# Power.net
KiCad netlist of a schematic drawn in Altium Designer
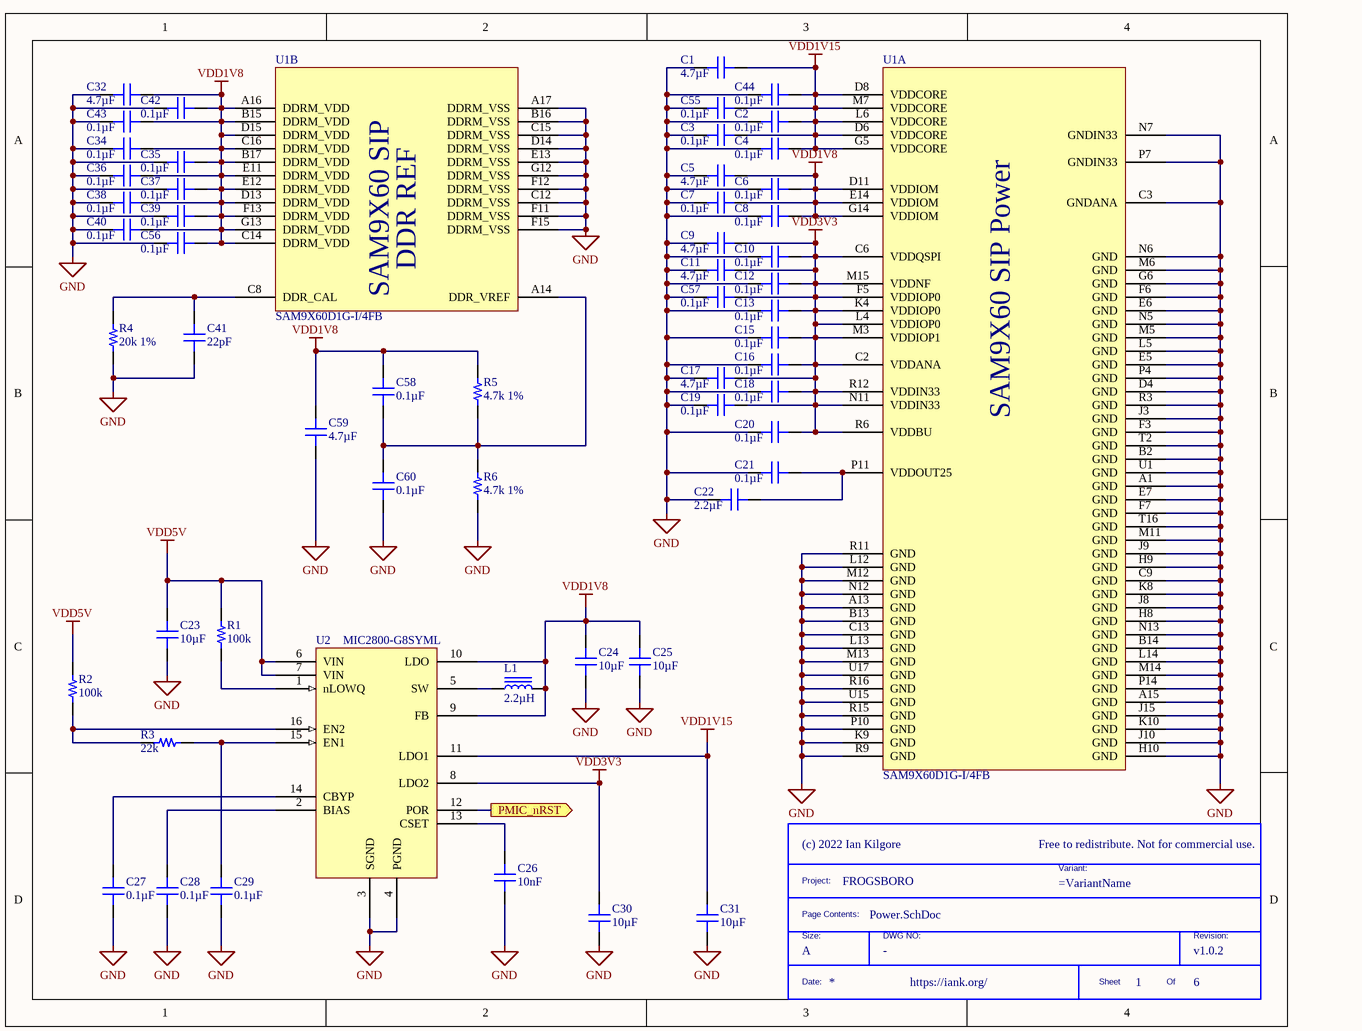
[diagram p0: Power.SchDoc]

(export (version "E")
  (design (tool "Eeschema 10.0.6"))
  (components
    (comp (ref "C1")
      (value "4.7µF")
      (footprint "CAP 0402_1005")
      (description "CAP CER 4.7UF 10V X5R 0402")
      (fields
        (field (name "PART NUMBER") "CL05A475KP5NRNC")
        (field (name "MANUFACTURER") "Samsung Electro-Mechanics")
      )
      (libsource (lib "Celestial Altium Library - altium_library") (part "Capacitor"))
    )
    (comp (ref "C2")
      (value "0.1µF")
      (footprint "CAP 0402_1005")
      (description "CAP CER 0.1UF 16V X5R 0402")
      (fields (field (name "PART NUMBER") "C0402C104K4PACTU") (field (name "MANUFACTURER") "KEMET"))
      (libsource (lib "Celestial Altium Library - altium_library") (part "Capacitor"))
    )
    (comp (ref "C3")
      (value "0.1µF")
      (footprint "CAP 0402_1005")
      (description "CAP CER 0.1UF 16V X5R 0402")
      (fields (field (name "PART NUMBER") "C0402C104K4PACTU") (field (name "MANUFACTURER") "KEMET"))
      (libsource (lib "Celestial Altium Library - altium_library") (part "Capacitor"))
    )
    (comp (ref "C4")
      (value "0.1µF")
      (footprint "CAP 0402_1005")
      (description "CAP CER 0.1UF 16V X5R 0402")
      (fields (field (name "PART NUMBER") "C0402C104K4PACTU") (field (name "MANUFACTURER") "KEMET"))
      (libsource (lib "Celestial Altium Library - altium_library") (part "Capacitor"))
    )
    (comp (ref "C5")
      (value "4.7µF")
      (footprint "CAP 0402_1005")
      (description "CAP CER 4.7UF 10V X5R 0402")
      (fields
        (field (name "PART NUMBER") "CL05A475KP5NRNC")
        (field (name "MANUFACTURER") "Samsung Electro-Mechanics")
      )
      (libsource (lib "Celestial Altium Library - altium_library") (part "Capacitor"))
    )
    (comp (ref "C6")
      (value "0.1µF")
      (footprint "CAP 0402_1005")
      (description "CAP CER 0.1UF 16V X5R 0402")
      (fields (field (name "PART NUMBER") "C0402C104K4PACTU") (field (name "MANUFACTURER") "KEMET"))
      (libsource (lib "Celestial Altium Library - altium_library") (part "Capacitor"))
    )
    (comp (ref "C7")
      (value "0.1µF")
      (footprint "CAP 0402_1005")
      (description "CAP CER 0.1UF 16V X5R 0402")
      (fields (field (name "PART NUMBER") "C0402C104K4PACTU") (field (name "MANUFACTURER") "KEMET"))
      (libsource (lib "Celestial Altium Library - altium_library") (part "Capacitor"))
    )
    (comp (ref "C8")
      (value "0.1µF")
      (footprint "CAP 0402_1005")
      (description "CAP CER 0.1UF 16V X5R 0402")
      (fields (field (name "PART NUMBER") "C0402C104K4PACTU") (field (name "MANUFACTURER") "KEMET"))
      (libsource (lib "Celestial Altium Library - altium_library") (part "Capacitor"))
    )
    (comp (ref "C9")
      (value "4.7µF")
      (footprint "CAP 0402_1005")
      (description "CAP CER 4.7UF 10V X5R 0402")
      (fields
        (field (name "PART NUMBER") "CL05A475KP5NRNC")
        (field (name "MANUFACTURER") "Samsung Electro-Mechanics")
      )
      (libsource (lib "Celestial Altium Library - altium_library") (part "Capacitor"))
    )
    (comp (ref "C10")
      (value "0.1µF")
      (footprint "CAP 0402_1005")
      (description "CAP CER 0.1UF 16V X5R 0402")
      (fields (field (name "PART NUMBER") "C0402C104K4PACTU") (field (name "MANUFACTURER") "KEMET"))
      (libsource (lib "Celestial Altium Library - altium_library") (part "Capacitor"))
    )
    (comp (ref "C11")
      (value "4.7µF")
      (footprint "CAP 0402_1005")
      (description "CAP CER 4.7UF 10V X5R 0402")
      (fields
        (field (name "PART NUMBER") "CL05A475KP5NRNC")
        (field (name "MANUFACTURER") "Samsung Electro-Mechanics")
      )
      (libsource (lib "Celestial Altium Library - altium_library") (part "Capacitor"))
    )
    (comp (ref "C12")
      (value "0.1µF")
      (footprint "CAP 0402_1005")
      (description "CAP CER 0.1UF 16V X5R 0402")
      (fields (field (name "PART NUMBER") "C0402C104K4PACTU") (field (name "MANUFACTURER") "KEMET"))
      (libsource (lib "Celestial Altium Library - altium_library") (part "Capacitor"))
    )
    (comp (ref "C13")
      (value "0.1µF")
      (footprint "CAP 0402_1005")
      (description "CAP CER 0.1UF 16V X5R 0402")
      (fields (field (name "PART NUMBER") "C0402C104K4PACTU") (field (name "MANUFACTURER") "KEMET"))
      (libsource (lib "Celestial Altium Library - altium_library") (part "Capacitor"))
    )
    (comp (ref "C15")
      (value "0.1µF")
      (footprint "CAP 0402_1005")
      (description "CAP CER 0.1UF 16V X5R 0402")
      (fields (field (name "PART NUMBER") "C0402C104K4PACTU") (field (name "MANUFACTURER") "KEMET"))
      (libsource (lib "Celestial Altium Library - altium_library") (part "Capacitor"))
    )
    (comp (ref "C16")
      (value "0.1µF")
      (footprint "CAP 0402_1005")
      (description "CAP CER 0.1UF 16V X5R 0402")
      (fields (field (name "PART NUMBER") "C0402C104K4PACTU") (field (name "MANUFACTURER") "KEMET"))
      (libsource (lib "Celestial Altium Library - altium_library") (part "Capacitor"))
    )
    (comp (ref "C17")
      (value "4.7µF")
      (footprint "CAP 0402_1005")
      (description "CAP CER 4.7UF 10V X5R 0402")
      (fields
        (field (name "PART NUMBER") "CL05A475KP5NRNC")
        (field (name "MANUFACTURER") "Samsung Electro-Mechanics")
      )
      (libsource (lib "Celestial Altium Library - altium_library") (part "Capacitor"))
    )
    (comp (ref "C18")
      (value "0.1µF")
      (footprint "CAP 0402_1005")
      (description "CAP CER 0.1UF 16V X5R 0402")
      (fields (field (name "PART NUMBER") "C0402C104K4PACTU") (field (name "MANUFACTURER") "KEMET"))
      (libsource (lib "Celestial Altium Library - altium_library") (part "Capacitor"))
    )
    (comp (ref "C19")
      (value "0.1µF")
      (footprint "CAP 0402_1005")
      (description "CAP CER 0.1UF 16V X5R 0402")
      (fields (field (name "PART NUMBER") "C0402C104K4PACTU") (field (name "MANUFACTURER") "KEMET"))
      (libsource (lib "Celestial Altium Library - altium_library") (part "Capacitor"))
    )
    (comp (ref "C20")
      (value "0.1µF")
      (footprint "CAP 0402_1005")
      (description "CAP CER 0.1UF 16V X5R 0402")
      (fields (field (name "PART NUMBER") "C0402C104K4PACTU") (field (name "MANUFACTURER") "KEMET"))
      (libsource (lib "Celestial Altium Library - altium_library") (part "Capacitor"))
    )
    (comp (ref "C21")
      (value "0.1µF")
      (footprint "CAP 0402_1005")
      (description "CAP CER 0.1UF 16V X5R 0402")
      (fields (field (name "PART NUMBER") "C0402C104K4PACTU") (field (name "MANUFACTURER") "KEMET"))
      (libsource (lib "Celestial Altium Library - altium_library") (part "Capacitor"))
    )
    (comp (ref "C22")
      (value "2.2µF")
      (footprint "CAP 0402_1005")
      (description "CAP CER 2.2UF 10V X5R 0402")
      (fields
        (field (name "PART NUMBER") "C1005X5R1A225K050BC")
        (field (name "MANUFACTURER") "TDK Corporation")
      )
      (libsource (lib "Celestial Altium Library - altium_library") (part "Capacitor"))
    )
    (comp (ref "C23")
      (value "10µF")
      (footprint "CAP 0805_2012")
      (description "CAP CER 10UF 10V X5R 0805")
      (fields
        (field (name "PART NUMBER") "CL21A106KPCLQNC")
        (field (name "MANUFACTURER") "Samsung Electro-Mechanics")
      )
      (libsource (lib "Celestial Altium Library - altium_library") (part "Capacitor"))
    )
    (comp (ref "C24")
      (value "10µF")
      (footprint "CAP 0805_2012")
      (description "CAP CER 10UF 10V X5R 0805")
      (fields
        (field (name "PART NUMBER") "CL21A106KPCLQNC")
        (field (name "MANUFACTURER") "Samsung Electro-Mechanics")
      )
      (libsource (lib "Celestial Altium Library - altium_library") (part "Capacitor"))
    )
    (comp (ref "C25")
      (value "10µF")
      (footprint "CAP 0805_2012")
      (description "CAP CER 10UF 10V X5R 0805")
      (fields
        (field (name "PART NUMBER") "CL21A106KPCLQNC")
        (field (name "MANUFACTURER") "Samsung Electro-Mechanics")
      )
      (libsource (lib "Celestial Altium Library - altium_library") (part "Capacitor"))
    )
    (comp (ref "C26")
      (value "10nF")
      (footprint "CAP 0402_1005")
      (description "CAP CER 0402 10NF 16V X7R 10%")
      (fields (field (name "PART NUMBER") "C0402C103K4RECAUTO") (field (name "MANUFACTURER") "KEMET"))
      (libsource (lib "Celestial Altium Library - altium_library") (part "Capacitor"))
    )
    (comp (ref "C27")
      (value "0.1µF")
      (footprint "CAP 0402_1005")
      (description "CAP CER 0.1UF 16V X5R 0402")
      (fields (field (name "PART NUMBER") "C0402C104K4PACTU") (field (name "MANUFACTURER") "KEMET"))
      (libsource (lib "Celestial Altium Library - altium_library") (part "Capacitor"))
    )
    (comp (ref "C28")
      (value "0.1µF")
      (footprint "CAP 0402_1005")
      (description "CAP CER 0.1UF 16V X5R 0402")
      (fields (field (name "PART NUMBER") "C0402C104K4PACTU") (field (name "MANUFACTURER") "KEMET"))
      (libsource (lib "Celestial Altium Library - altium_library") (part "Capacitor"))
    )
    (comp (ref "C29")
      (value "0.1µF")
      (footprint "CAP 0402_1005")
      (description "CAP CER 0.1UF 16V X5R 0402")
      (fields (field (name "PART NUMBER") "C0402C104K4PACTU") (field (name "MANUFACTURER") "KEMET"))
      (libsource (lib "Celestial Altium Library - altium_library") (part "Capacitor"))
    )
    (comp (ref "C30")
      (value "10µF")
      (footprint "CAP 0805_2012")
      (description "CAP CER 10UF 10V X5R 0805")
      (fields
        (field (name "PART NUMBER") "CL21A106KPCLQNC")
        (field (name "MANUFACTURER") "Samsung Electro-Mechanics")
      )
      (libsource (lib "Celestial Altium Library - altium_library") (part "Capacitor"))
    )
    (comp (ref "C31")
      (value "10µF")
      (footprint "CAP 0805_2012")
      (description "CAP CER 10UF 10V X5R 0805")
      (fields
        (field (name "PART NUMBER") "CL21A106KPCLQNC")
        (field (name "MANUFACTURER") "Samsung Electro-Mechanics")
      )
      (libsource (lib "Celestial Altium Library - altium_library") (part "Capacitor"))
    )
    (comp (ref "C32")
      (value "4.7µF")
      (footprint "CAP 0402_1005")
      (description "CAP CER 4.7UF 10V X5R 0402")
      (fields
        (field (name "PART NUMBER") "CL05A475KP5NRNC")
        (field (name "MANUFACTURER") "Samsung Electro-Mechanics")
      )
      (libsource (lib "Celestial Altium Library - altium_library") (part "Capacitor"))
    )
    (comp (ref "C34")
      (value "0.1µF")
      (footprint "CAP 0402_1005")
      (description "CAP CER 0.1UF 16V X5R 0402")
      (fields (field (name "PART NUMBER") "C0402C104K4PACTU") (field (name "MANUFACTURER") "KEMET"))
      (libsource (lib "Celestial Altium Library - altium_library") (part "Capacitor"))
    )
    (comp (ref "C35")
      (value "0.1µF")
      (footprint "CAP 0402_1005")
      (description "CAP CER 0.1UF 16V X5R 0402")
      (fields (field (name "PART NUMBER") "C0402C104K4PACTU") (field (name "MANUFACTURER") "KEMET"))
      (libsource (lib "Celestial Altium Library - altium_library") (part "Capacitor"))
    )
    (comp (ref "C36")
      (value "0.1µF")
      (footprint "CAP 0402_1005")
      (description "CAP CER 0.1UF 16V X5R 0402")
      (fields (field (name "PART NUMBER") "C0402C104K4PACTU") (field (name "MANUFACTURER") "KEMET"))
      (libsource (lib "Celestial Altium Library - altium_library") (part "Capacitor"))
    )
    (comp (ref "C37")
      (value "0.1µF")
      (footprint "CAP 0402_1005")
      (description "CAP CER 0.1UF 16V X5R 0402")
      (fields (field (name "PART NUMBER") "C0402C104K4PACTU") (field (name "MANUFACTURER") "KEMET"))
      (libsource (lib "Celestial Altium Library - altium_library") (part "Capacitor"))
    )
    (comp (ref "C38")
      (value "0.1µF")
      (footprint "CAP 0402_1005")
      (description "CAP CER 0.1UF 16V X5R 0402")
      (fields (field (name "PART NUMBER") "C0402C104K4PACTU") (field (name "MANUFACTURER") "KEMET"))
      (libsource (lib "Celestial Altium Library - altium_library") (part "Capacitor"))
    )
    (comp (ref "C39")
      (value "0.1µF")
      (footprint "CAP 0402_1005")
      (description "CAP CER 0.1UF 16V X5R 0402")
      (fields (field (name "PART NUMBER") "C0402C104K4PACTU") (field (name "MANUFACTURER") "KEMET"))
      (libsource (lib "Celestial Altium Library - altium_library") (part "Capacitor"))
    )
    (comp (ref "C40")
      (value "0.1µF")
      (footprint "CAP 0402_1005")
      (description "CAP CER 0.1UF 16V X5R 0402")
      (fields (field (name "PART NUMBER") "C0402C104K4PACTU") (field (name "MANUFACTURER") "KEMET"))
      (libsource (lib "Celestial Altium Library - altium_library") (part "Capacitor"))
    )
    (comp (ref "C41")
      (value "22pF")
      (footprint "CAP 0402_1005")
      (description "CAP CER 22PF 50V C0G/NP0 0402")
      (fields
        (field (name "PART NUMBER") "0402N220F500CT")
        (field (name "MANUFACTURER") "Walsin Technology Corporation")
      )
      (libsource (lib "Celestial Altium Library - altium_library") (part "Capacitor"))
    )
    (comp (ref "C42")
      (value "0.1µF")
      (footprint "CAP 0402_1005")
      (description "CAP CER 0.1UF 16V X5R 0402")
      (fields (field (name "PART NUMBER") "C0402C104K4PACTU") (field (name "MANUFACTURER") "KEMET"))
      (libsource (lib "Celestial Altium Library - altium_library") (part "Capacitor"))
    )
    (comp (ref "C43")
      (value "0.1µF")
      (footprint "CAP 0402_1005")
      (description "CAP CER 0.1UF 16V X5R 0402")
      (fields (field (name "PART NUMBER") "C0402C104K4PACTU") (field (name "MANUFACTURER") "KEMET"))
      (libsource (lib "Celestial Altium Library - altium_library") (part "Capacitor"))
    )
    (comp (ref "C44")
      (value "0.1µF")
      (footprint "CAP 0402_1005")
      (description "CAP CER 0.1UF 16V X5R 0402")
      (fields (field (name "PART NUMBER") "C0402C104K4PACTU") (field (name "MANUFACTURER") "KEMET"))
      (libsource (lib "Celestial Altium Library - altium_library") (part "Capacitor"))
    )
    (comp (ref "C55")
      (value "0.1µF")
      (footprint "CAP 0402_1005")
      (description "CAP CER 0.1UF 16V X5R 0402")
      (fields (field (name "PART NUMBER") "C0402C104K4PACTU") (field (name "MANUFACTURER") "KEMET"))
      (libsource (lib "Celestial Altium Library - altium_library") (part "Capacitor"))
    )
    (comp (ref "C56")
      (value "0.1µF")
      (footprint "CAP 0402_1005")
      (description "CAP CER 0.1UF 16V X5R 0402")
      (fields (field (name "PART NUMBER") "C0402C104K4PACTU") (field (name "MANUFACTURER") "KEMET"))
      (libsource (lib "Celestial Altium Library - altium_library") (part "Capacitor"))
    )
    (comp (ref "C57")
      (value "0.1µF")
      (footprint "CAP 0402_1005")
      (description "CAP CER 0.1UF 16V X5R 0402")
      (fields (field (name "PART NUMBER") "C0402C104K4PACTU") (field (name "MANUFACTURER") "KEMET"))
      (libsource (lib "Celestial Altium Library - altium_library") (part "Capacitor"))
    )
    (comp (ref "C58")
      (value "0.1µF")
      (footprint "CAP 0402_1005")
      (description "CAP CER 0.1UF 16V X5R 0402")
      (fields (field (name "PART NUMBER") "C0402C104K4PACTU") (field (name "MANUFACTURER") "KEMET"))
      (libsource (lib "Celestial Altium Library - altium_library") (part "Capacitor"))
    )
    (comp (ref "C59")
      (value "4.7µF")
      (footprint "CAP 0402_1005")
      (description "CAP CER 4.7UF 10V X5R 0402")
      (fields
        (field (name "PART NUMBER") "CL05A475KP5NRNC")
        (field (name "MANUFACTURER") "Samsung Electro-Mechanics")
      )
      (libsource (lib "Celestial Altium Library - altium_library") (part "Capacitor"))
    )
    (comp (ref "C60")
      (value "0.1µF")
      (footprint "CAP 0402_1005")
      (description "CAP CER 0.1UF 16V X5R 0402")
      (fields (field (name "PART NUMBER") "C0402C104K4PACTU") (field (name "MANUFACTURER") "KEMET"))
      (libsource (lib "Celestial Altium Library - altium_library") (part "Capacitor"))
    )
    (comp (ref "L1")
      (value "2.2µH")
      (footprint "IND 0806_2016")
      (description "FIXED IND 2.2UH 2.5A 87MOHM SMD")
      (fields
        (field (name "PART NUMBER") "CIGT201610EH2R2MNE")
        (field (name "MANUFACTURER") "Samsung Electro-Mechanics")
      )
      (libsource (lib "Celestial Altium Library - altium_library") (part "Inductor"))
    )
    (comp (ref "R1")
      (value "100k")
      (footprint "RES 0402_1005")
      (description "RES SMD 100K OHM 1% 1/16W 0402")
      (fields (field (name "PART NUMBER") "CRCW0402100KFKEDC") (field (name "MANUFACTURER") "Vishay Dale"))
      (libsource (lib "Celestial Altium Library - altium_library") (part "Resistor"))
    )
    (comp (ref "R2")
      (value "100k")
      (footprint "RES 0402_1005")
      (description "RES SMD 100K OHM 1% 1/16W 0402")
      (fields (field (name "PART NUMBER") "CRCW0402100KFKEDC") (field (name "MANUFACTURER") "Vishay Dale"))
      (libsource (lib "Celestial Altium Library - altium_library") (part "Resistor"))
    )
    (comp (ref "R3")
      (value "22k")
      (footprint "RES 0402_1005")
      (description "RES SMD 22K OHM 1% 1/16W 0402")
      (fields (field (name "PART NUMBER") "CR0402-FX-2202GLF") (field (name "MANUFACTURER") "Bourns Inc."))
      (libsource (lib "Celestial Altium Library - altium_library") (part "Resistor"))
    )
    (comp (ref "R4")
      (value "20k 1%")
      (footprint "RES 0402_1005")
      (description "RES SMD 20K OHM 1% 1/16W 0402")
      (fields (field (name "PART NUMBER") "CR0402-FX-2002GLF") (field (name "MANUFACTURER") "Bourns Inc."))
      (libsource (lib "Celestial Altium Library - altium_library") (part "Resistor"))
    )
    (comp (ref "R5")
      (value "4.7k 1%")
      (footprint "RES 0402_1005")
      (description "RES SMD 4.7K OHM 1% 1/16W 0402")
      (fields (field (name "PART NUMBER") "CR0402-FX-4701GLF") (field (name "MANUFACTURER") "Bourns Inc."))
      (libsource (lib "Celestial Altium Library - altium_library") (part "Resistor"))
    )
    (comp (ref "R6")
      (value "4.7k 1%")
      (footprint "RES 0402_1005")
      (description "RES SMD 4.7K OHM 1% 1/16W 0402")
      (fields (field (name "PART NUMBER") "CR0402-FX-4701GLF") (field (name "MANUFACTURER") "Bourns Inc."))
      (libsource (lib "Celestial Altium Library - altium_library") (part "Resistor"))
    )
    (comp (ref "U1")
      (value "SAM9X60D1G-I/4FB")
      (footprint "FROGSBORO:BGA233C80P17X17_1400X1400X120")
      (description "ARM926 MPU, 1GBIT DDR2, BGA, IND TEMP")
      (fields
        (field (name "MANUFACTURER") "Microchip")
        (field (name "MANUFACTURER PART NUMBER") "SAM9X60D6K-I/4GB")
      )
      (libsource (lib "FROGSBORO") (part "SAM9X60D1G-I/4FB"))
    )
    (comp (ref "U2")
      (value "MIC2800-G8SYML")
      (footprint "FROGSBORO:QFN50P300X300X90-16N")
      (description "DC-DC + 2 Linear Regulators with LowQ Mode & POR 16 VQFN 3x3x0.90mm T/R RoHS Compliant: Yes")
      (fields
        (field (name "MANUFACTURER") "Microchip")
        (field (name "MANUFACTURER PART NUMBER") "MIC2800-G8SYML-TR")
      )
      (libsource (lib "FROGSBORO") (part "MIC2800-G8SYML-TR"))
    )
  )
  (nets
    (net (code "1") (name "/PMIC_nRST") (class "Default")
      (node (ref "U2") (pin "12") (pinfunction "POR_12") (pintype "open_collector"))
    )
    (net (code "2") (name "GND") (class "Default")
      (node (ref "C1") (pin "1") (pinfunction "1_1") (pintype "passive"))
      (node (ref "C10") (pin "2") (pinfunction "2_2") (pintype "passive"))
      (node (ref "C11") (pin "1") (pinfunction "1_1") (pintype "passive"))
      (node (ref "C12") (pin "2") (pinfunction "2_2") (pintype "passive"))
      (node (ref "C13") (pin "2") (pinfunction "2_2") (pintype "passive"))
      (node (ref "C15") (pin "2") (pinfunction "2_2") (pintype "passive"))
      (node (ref "C16") (pin "2") (pinfunction "2_2") (pintype "passive"))
      (node (ref "C17") (pin "1") (pinfunction "1_1") (pintype "passive"))
      (node (ref "C18") (pin "2") (pinfunction "2_2") (pintype "passive"))
      (node (ref "C19") (pin "2") (pinfunction "2_2") (pintype "passive"))
      (node (ref "C2") (pin "2") (pinfunction "2_2") (pintype "passive"))
      (node (ref "C20") (pin "2") (pinfunction "2_2") (pintype "passive"))
      (node (ref "C21") (pin "2") (pinfunction "2_2") (pintype "passive"))
      (node (ref "C22") (pin "2") (pinfunction "2_2") (pintype "passive"))
      (node (ref "C23") (pin "1") (pinfunction "1_1") (pintype "passive"))
      (node (ref "C24") (pin "1") (pinfunction "1_1") (pintype "passive"))
      (node (ref "C25") (pin "1") (pinfunction "1_1") (pintype "passive"))
      (node (ref "C26") (pin "1") (pinfunction "1_1") (pintype "passive"))
      (node (ref "C27") (pin "1") (pinfunction "1_1") (pintype "passive"))
      (node (ref "C28") (pin "1") (pinfunction "1_1") (pintype "passive"))
      (node (ref "C29") (pin "1") (pinfunction "1_1") (pintype "passive"))
      (node (ref "C3") (pin "2") (pinfunction "2_2") (pintype "passive"))
      (node (ref "C30") (pin "1") (pinfunction "1_1") (pintype "passive"))
      (node (ref "C31") (pin "1") (pinfunction "1_1") (pintype "passive"))
      (node (ref "C32") (pin "1") (pinfunction "1_1") (pintype "passive"))
      (node (ref "C34") (pin "2") (pinfunction "2_2") (pintype "passive"))
      (node (ref "C35") (pin "2") (pinfunction "2_2") (pintype "passive"))
      (node (ref "C36") (pin "2") (pinfunction "2_2") (pintype "passive"))
      (node (ref "C37") (pin "2") (pinfunction "2_2") (pintype "passive"))
      (node (ref "C38") (pin "2") (pinfunction "2_2") (pintype "passive"))
      (node (ref "C39") (pin "2") (pinfunction "2_2") (pintype "passive"))
      (node (ref "C4") (pin "2") (pinfunction "2_2") (pintype "passive"))
      (node (ref "C40") (pin "2") (pinfunction "2_2") (pintype "passive"))
      (node (ref "C41") (pin "1") (pinfunction "1_1") (pintype "passive"))
      (node (ref "C42") (pin "2") (pinfunction "2_2") (pintype "passive"))
      (node (ref "C43") (pin "2") (pinfunction "2_2") (pintype "passive"))
      (node (ref "C44") (pin "2") (pinfunction "2_2") (pintype "passive"))
      (node (ref "C5") (pin "1") (pinfunction "1_1") (pintype "passive"))
      (node (ref "C55") (pin "2") (pinfunction "2_2") (pintype "passive"))
      (node (ref "C56") (pin "2") (pinfunction "2_2") (pintype "passive"))
      (node (ref "C57") (pin "2") (pinfunction "2_2") (pintype "passive"))
      (node (ref "C59") (pin "1") (pinfunction "1_1") (pintype "passive"))
      (node (ref "C6") (pin "2") (pinfunction "2_2") (pintype "passive"))
      (node (ref "C60") (pin "2") (pinfunction "2_2") (pintype "passive"))
      (node (ref "C7") (pin "2") (pinfunction "2_2") (pintype "passive"))
      (node (ref "C8") (pin "2") (pinfunction "2_2") (pintype "passive"))
      (node (ref "C9") (pin "1") (pinfunction "1_1") (pintype "passive"))
      (node (ref "R4") (pin "1") (pinfunction "1_1") (pintype "passive"))
      (node (ref "R6") (pin "1") (pinfunction "1_1") (pintype "passive"))
      (node (ref "U1") (pin "A1") (pinfunction "GND_A1") (pintype "power_in"))
      (node (ref "U1") (pin "A13") (pinfunction "GND_A13") (pintype "power_in"))
      (node (ref "U1") (pin "A15") (pinfunction "GND_A15") (pintype "power_in"))
      (node (ref "U1") (pin "A17") (pinfunction "DDRM_VSS_A17") (pintype "power_in"))
      (node (ref "U1") (pin "B13") (pinfunction "GND_B13") (pintype "power_in"))
      (node (ref "U1") (pin "B14") (pinfunction "GND_B14") (pintype "power_in"))
      (node (ref "U1") (pin "B16") (pinfunction "DDRM_VSS_B16") (pintype "power_in"))
      (node (ref "U1") (pin "B2") (pinfunction "GND_B2") (pintype "power_in"))
      (node (ref "U1") (pin "C12") (pinfunction "DDRM_VSS_C12") (pintype "power_in"))
      (node (ref "U1") (pin "C13") (pinfunction "GND_C13") (pintype "power_in"))
      (node (ref "U1") (pin "C15") (pinfunction "DDRM_VSS_C15") (pintype "power_in"))
      (node (ref "U1") (pin "C3") (pinfunction "GNDANA_C3") (pintype "power_in"))
      (node (ref "U1") (pin "C9") (pinfunction "GND_C9") (pintype "power_in"))
      (node (ref "U1") (pin "D14") (pinfunction "DDRM_VSS_D14") (pintype "power_in"))
      (node (ref "U1") (pin "D4") (pinfunction "GND_D4") (pintype "power_in"))
      (node (ref "U1") (pin "E13") (pinfunction "DDRM_VSS_E13") (pintype "power_in"))
      (node (ref "U1") (pin "E5") (pinfunction "GND_E5") (pintype "power_in"))
      (node (ref "U1") (pin "E6") (pinfunction "GND_E6") (pintype "power_in"))
      (node (ref "U1") (pin "E7") (pinfunction "GND_E7") (pintype "power_in"))
      (node (ref "U1") (pin "F11") (pinfunction "DDRM_VSS_F11") (pintype "power_in"))
      (node (ref "U1") (pin "F12") (pinfunction "DDRM_VSS_F12") (pintype "power_in"))
      (node (ref "U1") (pin "F15") (pinfunction "DDRM_VSS_F15") (pintype "power_in"))
      (node (ref "U1") (pin "F3") (pinfunction "GND_F3") (pintype "power_in"))
      (node (ref "U1") (pin "F6") (pinfunction "GND_F6") (pintype "power_in"))
      (node (ref "U1") (pin "F7") (pinfunction "GND_F7") (pintype "power_in"))
      (node (ref "U1") (pin "G12") (pinfunction "DDRM_VSS_G12") (pintype "power_in"))
      (node (ref "U1") (pin "G6") (pinfunction "GND_G6") (pintype "power_in"))
      (node (ref "U1") (pin "H10") (pinfunction "GND_H10") (pintype "power_in"))
      (node (ref "U1") (pin "H8") (pinfunction "GND_H8") (pintype "power_in"))
      (node (ref "U1") (pin "H9") (pinfunction "GND_H9") (pintype "power_in"))
      (node (ref "U1") (pin "J10") (pinfunction "GND_J10") (pintype "power_in"))
      (node (ref "U1") (pin "J15") (pinfunction "GND_J15") (pintype "power_in"))
      (node (ref "U1") (pin "J3") (pinfunction "GND_J3") (pintype "power_in"))
      (node (ref "U1") (pin "J8") (pinfunction "GND_J8") (pintype "power_in"))
      (node (ref "U1") (pin "J9") (pinfunction "GND_J9") (pintype "power_in"))
      (node (ref "U1") (pin "K10") (pinfunction "GND_K10") (pintype "power_in"))
      (node (ref "U1") (pin "K8") (pinfunction "GND_K8") (pintype "power_in"))
      (node (ref "U1") (pin "K9") (pinfunction "GND_K9") (pintype "power_in"))
      (node (ref "U1") (pin "L12") (pinfunction "GND_L12") (pintype "power_in"))
      (node (ref "U1") (pin "L13") (pinfunction "GND_L13") (pintype "power_in"))
      (node (ref "U1") (pin "L14") (pinfunction "GND_L14") (pintype "power_in"))
      (node (ref "U1") (pin "L5") (pinfunction "GND_L5") (pintype "power_in"))
      (node (ref "U1") (pin "M11") (pinfunction "GND_M11") (pintype "power_in"))
      (node (ref "U1") (pin "M12") (pinfunction "GND_M12") (pintype "power_in"))
      (node (ref "U1") (pin "M13") (pinfunction "GND_M13") (pintype "power_in"))
      (node (ref "U1") (pin "M14") (pinfunction "GND_M14") (pintype "power_in"))
      (node (ref "U1") (pin "M5") (pinfunction "GND_M5") (pintype "power_in"))
      (node (ref "U1") (pin "M6") (pinfunction "GND_M6") (pintype "power_in"))
      (node (ref "U1") (pin "N12") (pinfunction "GND_N12") (pintype "power_in"))
      (node (ref "U1") (pin "N13") (pinfunction "GND_N13") (pintype "power_in"))
      (node (ref "U1") (pin "N5") (pinfunction "GND_N5") (pintype "power_in"))
      (node (ref "U1") (pin "N6") (pinfunction "GND_N6") (pintype "power_in"))
      (node (ref "U1") (pin "N7") (pinfunction "GNDIN33_N7") (pintype "power_in"))
      (node (ref "U1") (pin "P10") (pinfunction "GND_P10") (pintype "power_in"))
      (node (ref "U1") (pin "P14") (pinfunction "GND_P14") (pintype "power_in"))
      (node (ref "U1") (pin "P4") (pinfunction "GND_P4") (pintype "power_in"))
      (node (ref "U1") (pin "P7") (pinfunction "GNDIN33_P7") (pintype "power_in"))
      (node (ref "U1") (pin "R11") (pinfunction "GND_R11") (pintype "power_in"))
      (node (ref "U1") (pin "R15") (pinfunction "GND_R15") (pintype "power_in"))
      (node (ref "U1") (pin "R16") (pinfunction "GND_R16") (pintype "power_in"))
      (node (ref "U1") (pin "R3") (pinfunction "GND_R3") (pintype "power_in"))
      (node (ref "U1") (pin "R9") (pinfunction "GND_R9") (pintype "power_in"))
      (node (ref "U1") (pin "T16") (pinfunction "GND_T16") (pintype "power_in"))
      (node (ref "U1") (pin "T2") (pinfunction "GND_T2") (pintype "power_in"))
      (node (ref "U1") (pin "U1") (pinfunction "GND_U1") (pintype "power_in"))
      (node (ref "U1") (pin "U15") (pinfunction "GND_U15") (pintype "power_in"))
      (node (ref "U1") (pin "U17") (pinfunction "GND_U17") (pintype "power_in"))
      (node (ref "U2") (pin "3") (pinfunction "SGND_3") (pintype "power_in"))
      (node (ref "U2") (pin "4") (pinfunction "PGND_4") (pintype "power_in"))
    )
    (net (code "3") (name "Net-(U1A-VDDOUT25)") (class "Default")
      (node (ref "C21") (pin "1") (pinfunction "1_1") (pintype "passive"))
      (node (ref "C22") (pin "1") (pinfunction "1_1") (pintype "passive"))
      (node (ref "U1") (pin "P11") (pinfunction "VDDOUT25_P11") (pintype "power_in"))
    )
    (net (code "4") (name "Net-(U1B-DDR_CAL)") (class "Default")
      (node (ref "C41") (pin "2") (pinfunction "2_2") (pintype "passive"))
      (node (ref "R4") (pin "2") (pinfunction "2_2") (pintype "passive"))
      (node (ref "U1") (pin "C8") (pinfunction "DDR_CAL_C8") (pintype "passive"))
    )
    (net (code "5") (name "Net-(U1B-DDR_VREF)") (class "Default")
      (node (ref "C58") (pin "2") (pinfunction "2_2") (pintype "passive"))
      (node (ref "C60") (pin "1") (pinfunction "1_1") (pintype "passive"))
      (node (ref "R5") (pin "1") (pinfunction "1_1") (pintype "passive"))
      (node (ref "R6") (pin "2") (pinfunction "2_2") (pintype "passive"))
      (node (ref "U1") (pin "A14") (pinfunction "DDR_VREF_A14") (pintype "power_in"))
    )
    (net (code "6") (name "Net-(U2-BIAS)") (class "Default")
      (node (ref "C28") (pin "2") (pinfunction "2_2") (pintype "passive"))
      (node (ref "U2") (pin "2") (pinfunction "BIAS_2") (pintype "passive"))
    )
    (net (code "7") (name "Net-(U2-CBYP)") (class "Default")
      (node (ref "C27") (pin "2") (pinfunction "2_2") (pintype "passive"))
      (node (ref "U2") (pin "14") (pinfunction "CBYP_14") (pintype "passive"))
    )
    (net (code "8") (name "Net-(U2-CSET)") (class "Default")
      (node (ref "C26") (pin "2") (pinfunction "2_2") (pintype "passive"))
      (node (ref "U2") (pin "13") (pinfunction "CSET_13") (pintype "passive"))
    )
    (net (code "9") (name "Net-(U2-EN1)") (class "Default")
      (node (ref "C29") (pin "2") (pinfunction "2_2") (pintype "passive"))
      (node (ref "R3") (pin "1") (pinfunction "1_1") (pintype "passive"))
      (node (ref "U2") (pin "15") (pinfunction "EN1_15") (pintype "input"))
    )
    (net (code "10") (name "Net-(U2-EN2)") (class "Default")
      (node (ref "R2") (pin "1") (pinfunction "1_1") (pintype "passive"))
      (node (ref "R3") (pin "2") (pinfunction "2_2") (pintype "passive"))
      (node (ref "U2") (pin "16") (pinfunction "EN2_16") (pintype "input"))
    )
    (net (code "11") (name "Net-(U2-SW)") (class "Default")
      (node (ref "L1") (pin "1") (pinfunction "1_1") (pintype "passive"))
      (node (ref "U2") (pin "5") (pinfunction "SW_5") (pintype "power_in"))
    )
    (net (code "12") (name "Net-(U2-nLOWQ)") (class "Default")
      (node (ref "R1") (pin "1") (pinfunction "1_1") (pintype "passive"))
      (node (ref "U2") (pin "1") (pinfunction "nLOWQ_1") (pintype "input"))
    )
    (net (code "13") (name "VDD1V8") (class "Default")
      (node (ref "C24") (pin "2") (pinfunction "2_2") (pintype "passive"))
      (node (ref "C25") (pin "2") (pinfunction "2_2") (pintype "passive"))
      (node (ref "C32") (pin "2") (pinfunction "2_2") (pintype "passive"))
      (node (ref "C34") (pin "1") (pinfunction "1_1") (pintype "passive"))
      (node (ref "C35") (pin "1") (pinfunction "1_1") (pintype "passive"))
      (node (ref "C36") (pin "1") (pinfunction "1_1") (pintype "passive"))
      (node (ref "C37") (pin "1") (pinfunction "1_1") (pintype "passive"))
      (node (ref "C38") (pin "1") (pinfunction "1_1") (pintype "passive"))
      (node (ref "C39") (pin "1") (pinfunction "1_1") (pintype "passive"))
      (node (ref "C40") (pin "1") (pinfunction "1_1") (pintype "passive"))
      (node (ref "C42") (pin "1") (pinfunction "1_1") (pintype "passive"))
      (node (ref "C43") (pin "1") (pinfunction "1_1") (pintype "passive"))
      (node (ref "C5") (pin "2") (pinfunction "2_2") (pintype "passive"))
      (node (ref "C56") (pin "1") (pinfunction "1_1") (pintype "passive"))
      (node (ref "C58") (pin "1") (pinfunction "1_1") (pintype "passive"))
      (node (ref "C59") (pin "2") (pinfunction "2_2") (pintype "passive"))
      (node (ref "C6") (pin "1") (pinfunction "1_1") (pintype "passive"))
      (node (ref "C7") (pin "1") (pinfunction "1_1") (pintype "passive"))
      (node (ref "C8") (pin "1") (pinfunction "1_1") (pintype "passive"))
      (node (ref "L1") (pin "2") (pinfunction "2_2") (pintype "passive"))
      (node (ref "R5") (pin "2") (pinfunction "2_2") (pintype "passive"))
      (node (ref "U1") (pin "A16") (pinfunction "DDRM_VDD_A16") (pintype "power_in"))
      (node (ref "U1") (pin "B15") (pinfunction "DDRM_VDD_B15") (pintype "power_in"))
      (node (ref "U1") (pin "B17") (pinfunction "DDRM_VDD_B17") (pintype "power_in"))
      (node (ref "U1") (pin "C14") (pinfunction "DDRM_VDD_C14") (pintype "power_in"))
      (node (ref "U1") (pin "C16") (pinfunction "DDRM_VDD_C16") (pintype "power_in"))
      (node (ref "U1") (pin "D11") (pinfunction "VDDIOM_D11") (pintype "power_in"))
      (node (ref "U1") (pin "D13") (pinfunction "DDRM_VDD_D13") (pintype "power_in"))
      (node (ref "U1") (pin "D15") (pinfunction "DDRM_VDD_D15") (pintype "power_in"))
      (node (ref "U1") (pin "E11") (pinfunction "DDRM_VDD_E11") (pintype "power_in"))
      (node (ref "U1") (pin "E12") (pinfunction "DDRM_VDD_E12") (pintype "power_in"))
      (node (ref "U1") (pin "E14") (pinfunction "VDDIOM_E14") (pintype "power_in"))
      (node (ref "U1") (pin "F13") (pinfunction "DDRM_VDD_F13") (pintype "power_in"))
      (node (ref "U1") (pin "G13") (pinfunction "DDRM_VDD_G13") (pintype "power_in"))
      (node (ref "U1") (pin "G14") (pinfunction "VDDIOM_G14") (pintype "power_in"))
      (node (ref "U2") (pin "10") (pinfunction "LDO_10") (pintype "power_in"))
      (node (ref "U2") (pin "9") (pinfunction "FB_9") (pintype "passive"))
    )
    (net (code "14") (name "VDD1V15") (class "Default")
      (node (ref "C1") (pin "2") (pinfunction "2_2") (pintype "passive"))
      (node (ref "C2") (pin "1") (pinfunction "1_1") (pintype "passive"))
      (node (ref "C3") (pin "1") (pinfunction "1_1") (pintype "passive"))
      (node (ref "C31") (pin "2") (pinfunction "2_2") (pintype "passive"))
      (node (ref "C4") (pin "1") (pinfunction "1_1") (pintype "passive"))
      (node (ref "C44") (pin "1") (pinfunction "1_1") (pintype "passive"))
      (node (ref "C55") (pin "1") (pinfunction "1_1") (pintype "passive"))
      (node (ref "U1") (pin "D6") (pinfunction "VDDCORE_D6") (pintype "power_in"))
      (node (ref "U1") (pin "D8") (pinfunction "VDDCORE_D8") (pintype "power_in"))
      (node (ref "U1") (pin "G5") (pinfunction "VDDCORE_G5") (pintype "power_in"))
      (node (ref "U1") (pin "L6") (pinfunction "VDDCORE_L6") (pintype "power_in"))
      (node (ref "U1") (pin "M7") (pinfunction "VDDCORE_M7") (pintype "power_in"))
      (node (ref "U2") (pin "11") (pinfunction "LDO1_11") (pintype "power_in"))
    )
    (net (code "15") (name "VDD3V3") (class "Default")
      (node (ref "C10") (pin "1") (pinfunction "1_1") (pintype "passive"))
      (node (ref "C11") (pin "2") (pinfunction "2_2") (pintype "passive"))
      (node (ref "C12") (pin "1") (pinfunction "1_1") (pintype "passive"))
      (node (ref "C13") (pin "1") (pinfunction "1_1") (pintype "passive"))
      (node (ref "C15") (pin "1") (pinfunction "1_1") (pintype "passive"))
      (node (ref "C16") (pin "1") (pinfunction "1_1") (pintype "passive"))
      (node (ref "C17") (pin "2") (pinfunction "2_2") (pintype "passive"))
      (node (ref "C18") (pin "1") (pinfunction "1_1") (pintype "passive"))
      (node (ref "C19") (pin "1") (pinfunction "1_1") (pintype "passive"))
      (node (ref "C20") (pin "1") (pinfunction "1_1") (pintype "passive"))
      (node (ref "C30") (pin "2") (pinfunction "2_2") (pintype "passive"))
      (node (ref "C57") (pin "1") (pinfunction "1_1") (pintype "passive"))
      (node (ref "C9") (pin "2") (pinfunction "2_2") (pintype "passive"))
      (node (ref "U1") (pin "C2") (pinfunction "VDDANA_C2") (pintype "power_in"))
      (node (ref "U1") (pin "C6") (pinfunction "VDDQSPI_C6") (pintype "power_in"))
      (node (ref "U1") (pin "F5") (pinfunction "VDDIOP0_F5") (pintype "power_in"))
      (node (ref "U1") (pin "K4") (pinfunction "VDDIOP0_K4") (pintype "power_in"))
      (node (ref "U1") (pin "L4") (pinfunction "VDDIOP0_L4") (pintype "power_in"))
      (node (ref "U1") (pin "M15") (pinfunction "VDDNF_M15") (pintype "power_in"))
      (node (ref "U1") (pin "M3") (pinfunction "VDDIOP1_M3") (pintype "power_in"))
      (node (ref "U1") (pin "N11") (pinfunction "VDDIN33_N11") (pintype "power_in"))
      (node (ref "U1") (pin "R12") (pinfunction "VDDIN33_R12") (pintype "power_in"))
      (node (ref "U1") (pin "R6") (pinfunction "VDDBU_R6") (pintype "power_in"))
      (node (ref "U2") (pin "8") (pinfunction "LDO2_8") (pintype "power_in"))
    )
    (net (code "16") (name "VDD5V") (class "Default")
      (node (ref "C23") (pin "2") (pinfunction "2_2") (pintype "passive"))
      (node (ref "R1") (pin "2") (pinfunction "2_2") (pintype "passive"))
      (node (ref "R2") (pin "2") (pinfunction "2_2") (pintype "passive"))
      (node (ref "U2") (pin "6") (pinfunction "VIN_6") (pintype "power_in"))
      (node (ref "U2") (pin "7") (pinfunction "VIN_7") (pintype "power_in"))
    )
  )
)
